# FPGA_CFG.net
KiCad netlist of a schematic drawn in Altium Designer
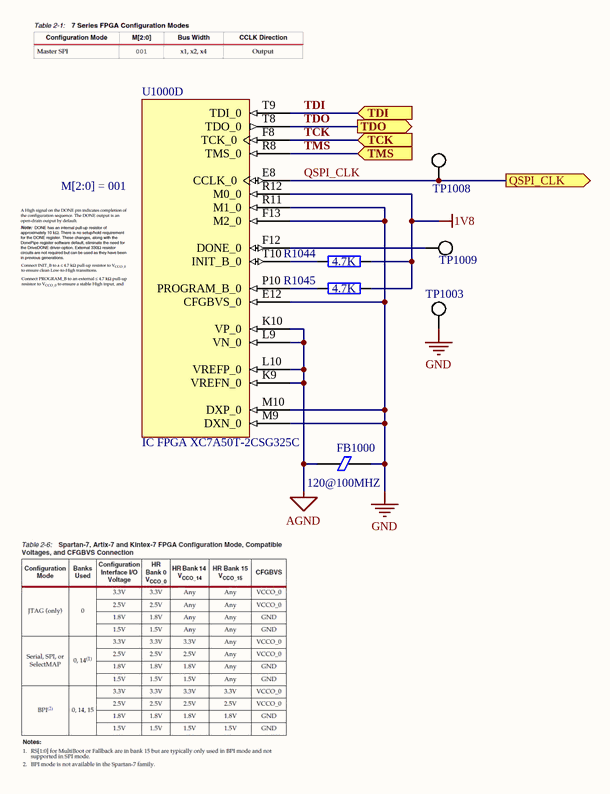
[diagram p0: FPGA_CFG.SchDoc]

(export (version "E")
  (design (tool "Eeschema 10.0.6"))
  (components
    (comp (ref "FB1000")
      (value "120@100MHZ")
      (footprint "GEN_R_0402")
      (fields (field (name "HOUSE PART NUMBER") "BLM15PX121SN1D") (field (name "MANUFACTURER") "Murata"))
      (libsource (lib "DSO") (part "FERRITE BEAD 120 OHM 0402"))
    )
    (comp (ref "R1044")
      (value "4.7K")
      (footprint "GEN_R_0201")
      (fields
        (field (name "TOLERANCE") "1%")
        (field (name "HOUSE PART NUMBER") "R-4.7K-0201-1%-001")
        (field (name "MANUFACTURER") "Yageo")
      )
      (libsource (lib "DSO") (part "RES 4.7K OHM 1% 1/20W 0201"))
    )
    (comp (ref "R1045")
      (value "4.7K")
      (footprint "GEN_R_0201")
      (fields
        (field (name "TOLERANCE") "1%")
        (field (name "HOUSE PART NUMBER") "R-4.7K-0201-1%-001")
        (field (name "MANUFACTURER") "Yageo")
      )
      (libsource (lib "DSO") (part "RES 4.7K OHM 1% 1/20W 0201"))
    )
    (comp (ref "TP1003") (value "PCB") (footprint "GEN_TP_PCB") (libsource (lib "DSO") (part "TP PCB 1mm")))
    (comp (ref "TP1008") (value "PCB") (footprint "GEN_TP_PCB") (libsource (lib "DSO") (part "TP PCB 1mm")))
    (comp (ref "TP1009") (value "PCB") (footprint "GEN_TP_PCB") (libsource (lib "DSO") (part "TP PCB 1mm")))
    (comp (ref "U1000")
      (value "IC FPGA XC7A50T-2CSG325C")
      (footprint "XILINX_XC7A50T-2CSG325C")
      (description "Artix-7 FPGA, 150 User I/Os, 4 GTP, 324-Ball BGA, Speed Grade 2, Commercial Grade, Pb-Free")
      (fields (field (name "MANUFACTURER") "Xilinx") (field (name "HOUSE PART NUMBER") "XC7A50T-2CSG325C"))
      (libsource (lib "DSO") (part "IC FPGA XC7A50T-2CSG325C"))
    )
  )
  (nets
    (net (code "1") (name "/QSPI_CLK") (class "Default")
      (node (ref "TP1008") (pin "1") (pinfunction "1_1") (pintype "passive"))
      (node (ref "U1000") (pin "E8") (pinfunction "CCLK_0_E8") (pintype "bidirectional"))
    )
    (net (code "2") (name "/TCK") (class "Default")
      (node (ref "U1000") (pin "F8") (pinfunction "TCK_0_F8") (pintype "input"))
    )
    (net (code "3") (name "/TDI") (class "Default")
      (node (ref "U1000") (pin "T9") (pinfunction "TDI_0_T9") (pintype "input"))
    )
    (net (code "4") (name "/TDO") (class "Default")
      (node (ref "U1000") (pin "T8") (pinfunction "TDO_0_T8") (pintype "output"))
    )
    (net (code "5") (name "/TMS") (class "Default")
      (node (ref "U1000") (pin "R8") (pinfunction "TMS_0_R8") (pintype "input"))
    )
    (net (code "6") (name "1V8") (class "Default")
      (node (ref "R1044") (pin "2") (pinfunction "2_2") (pintype "passive"))
      (node (ref "R1045") (pin "2") (pinfunction "2_2") (pintype "passive"))
      (node (ref "U1000") (pin "R12") (pinfunction "M0_0_R12") (pintype "input"))
    )
    (net (code "7") (name "AGND") (class "Default")
      (node (ref "FB1000") (pin "1") (pinfunction "1_1") (pintype "passive"))
      (node (ref "U1000") (pin "K10") (pinfunction "VP_0_K10") (pintype "input"))
      (node (ref "U1000") (pin "K9") (pinfunction "VREFN_0_K9") (pintype "input"))
      (node (ref "U1000") (pin "L10") (pinfunction "VREFP_0_L10") (pintype "input"))
      (node (ref "U1000") (pin "L9") (pinfunction "VN_0_L9") (pintype "input"))
    )
    (net (code "8") (name "GND") (class "Default")
      (node (ref "FB1000") (pin "2") (pinfunction "2_2") (pintype "passive"))
      (node (ref "TP1003") (pin "1") (pinfunction "1_1") (pintype "passive"))
      (node (ref "U1000") (pin "E12") (pinfunction "CFGBVS_0_E12") (pintype "input"))
      (node (ref "U1000") (pin "F13") (pinfunction "M2_0_F13") (pintype "input"))
      (node (ref "U1000") (pin "M10") (pinfunction "DXP_0_M10") (pintype "input"))
      (node (ref "U1000") (pin "M9") (pinfunction "DXN_0_M9") (pintype "input"))
      (node (ref "U1000") (pin "R11") (pinfunction "M1_0_R11") (pintype "input"))
    )
    (net (code "9") (name "Net-(U1000D-DONE_0)") (class "Default")
      (node (ref "TP1009") (pin "1") (pinfunction "1_1") (pintype "passive"))
      (node (ref "U1000") (pin "F12") (pinfunction "DONE_0_F12") (pintype "bidirectional"))
    )
    (net (code "10") (name "Net-(U1000D-INIT_B_0)") (class "Default")
      (node (ref "R1044") (pin "1") (pinfunction "1_1") (pintype "passive"))
      (node (ref "U1000") (pin "T10") (pinfunction "INIT_B_0_T10") (pintype "bidirectional"))
    )
    (net (code "11") (name "Net-(U1000D-PROGRAM_B_0)") (class "Default")
      (node (ref "R1045") (pin "1") (pinfunction "1_1") (pintype "passive"))
      (node (ref "U1000") (pin "P10") (pinfunction "PROGRAM_B_0_P10") (pintype "input"))
    )
  )
)
